# PWM.net
KiCad netlist of a schematic drawn in Altium Designer
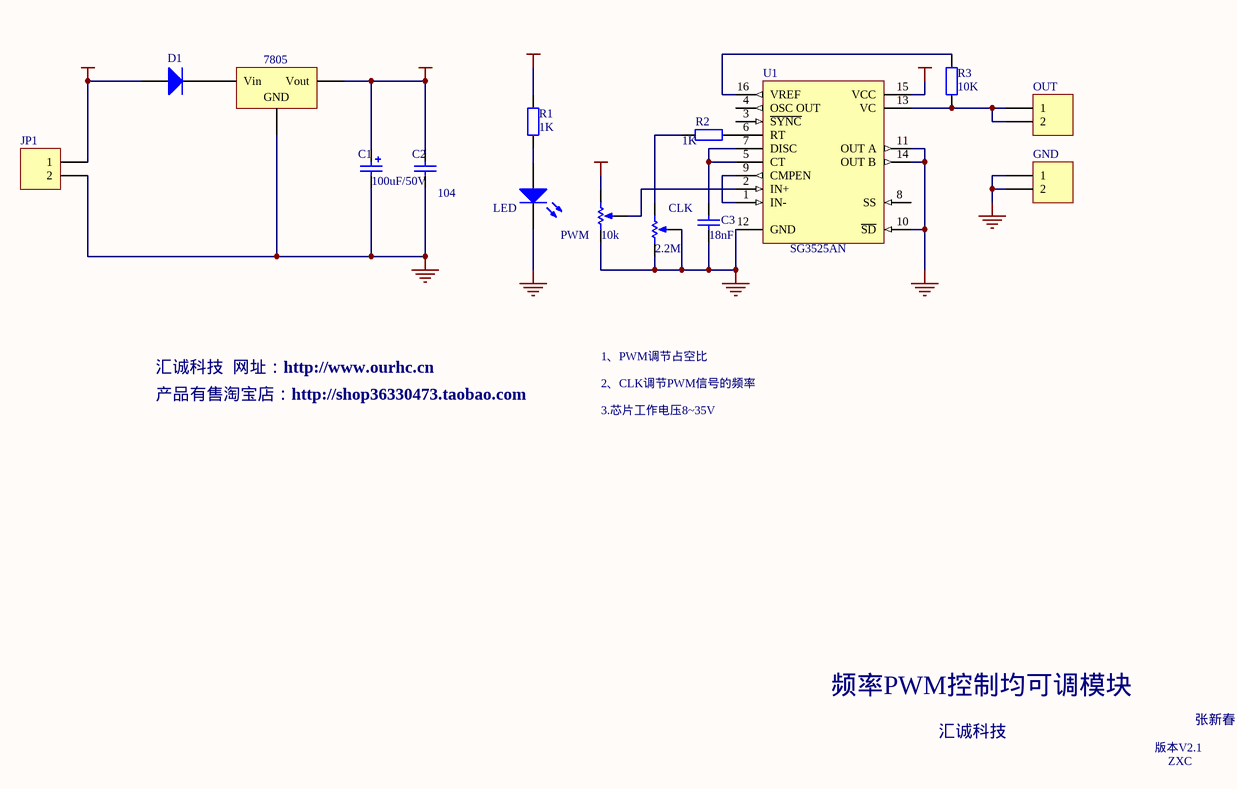
[diagram p0: 频率PWM控制均可调模块.SchDoc]

(export (version "E")
  (design (tool "Eeschema 10.0.6"))
  (components
    (comp (ref "7805")
      (value "SDWYG")
      (footprint "WYG")
      (description "三端稳压器")
      (fields (field (name "PUBLISHER") "Altium Limited"))
      (libsource (lib "zxcourhc") (part "SDWYG"))
    )
    (comp (ref "C1")
      (value "100uF/50V")
      (footprint "C-DJ-6")
      (description "电解电容")
      (fields (field (name "Comment") "DJDR") (field (name "PUBLISHER") "Altium Limited"))
      (libsource (lib "zxcourhc") (part "DJDR"))
    )
    (comp (ref "C2")
      (value "104")
      (footprint "CPDR")
      (description "瓷片电容")
      (fields (field (name "Comment") "CPDR") (field (name "PUBLISHER") "Altium Limited"))
      (libsource (lib "zxcourhc") (part "CPDR"))
    )
    (comp (ref "C3")
      (value "18nF")
      (footprint "CPDR")
      (description "Capacitor (Semiconductor SIM Model)")
      (fields (field (name "Comment") "Cap Semi") (field (name "PUBLISHER") "Altium Limited"))
      (libsource (lib "Miscellaneous Devices") (part "Cap Semi"))
    )
    (comp (ref "CLK")
      (value "2.2M")
      (footprint "SIP3-D")
      (description "Potentiometer")
      (fields (field (name "Comment") "RPot") (field (name "PUBLISHER") "Altium Limited"))
      (libsource (lib "Miscellaneous Devices") (part "RPot"))
    )
    (comp (ref "D1")
      (value "Diode 1N4007")
      (footprint "D-ZL-10")
      (description "1 Amp General Purpose Rectifier")
      (fields (field (name "PUBLISHER") "Altium Limited"))
      (libsource (lib "Miscellaneous Devices") (part "Diode 1N4007"))
    )
    (comp (ref "GND")
      (value "Header 2")
      (footprint "HDR1X2")
      (description "Header, 2-Pin")
      (fields (field (name "PUBLISHER") "Altium Limited"))
      (libsource (lib "Miscellaneous Connectors") (part "Header 2"))
    )
    (comp (ref "JP1")
      (value "PZ_2")
      (footprint "zxcourhc:JK128_2")
      (description "排针——2")
      (fields (field (name "PUBLISHER") "Altium Limited"))
      (libsource (lib "zxcourhc") (part "PZ_2"))
    )
    (comp (ref "LED")
      (value "LED2")
      (footprint "LED_D")
      (description "Typical RED, GREEN, YELLOW, AMBER GaAs LED")
      (fields (field (name "PUBLISHER") "Altium Limited"))
      (libsource (lib "Miscellaneous Devices") (part "LED2"))
    )
    (comp (ref "OUT")
      (value "Header 2")
      (footprint "HDR1X2")
      (description "Header, 2-Pin")
      (fields (field (name "PUBLISHER") "Altium Limited"))
      (libsource (lib "Miscellaneous Connectors") (part "Header 2"))
    )
    (comp (ref "PWM")
      (value "10k")
      (footprint "SIP3-D")
      (description "Potentiometer")
      (fields (field (name "Comment") "RPot") (field (name "PUBLISHER") "Altium Limited"))
      (libsource (lib "Miscellaneous Devices") (part "RPot"))
    )
    (comp (ref "R1")
      (value "1K")
      (footprint "AXIAL-0.4")
      (description "Resistor")
      (fields (field (name "Comment") "Res2") (field (name "PUBLISHER") "Altium Limited"))
      (libsource (lib "") (part "Res2_2"))
    )
    (comp (ref "R2")
      (value "1K")
      (footprint "AXIAL-0.4")
      (description "Resistor")
      (fields (field (name "Comment") "Res2") (field (name "PUBLISHER") "Altium Limited"))
      (libsource (lib "Miscellaneous Devices") (part "Res2"))
    )
    (comp (ref "R3")
      (value "10K")
      (footprint "AXIAL-0.4")
      (description "Resistor")
      (fields (field (name "Comment") "Res2") (field (name "PUBLISHER") "Altium Limited"))
      (libsource (lib "") (part "Res2_1"))
    )
    (comp (ref "U1")
      (value "SG3525AN")
      (footprint "DIP16")
      (description "Pulse Width Modulator Control Circuit")
      (fields (field (name "PUBLISHER") "Altium Limited"))
      (libsource (lib "ON Semi Power Mgt SMPS Controller") (part "SG3525AN"))
    )
  )
  (nets
    (net (code "1") (name "GND") (class "Default")
      (node (ref "7805") (pin "3") (pinfunction "GND_3") (pintype "passive"))
      (node (ref "C1") (pin "2") (pinfunction "2_2") (pintype "passive"))
      (node (ref "C2") (pin "1") (pinfunction "1_1") (pintype "passive"))
      (node (ref "C3") (pin "2") (pinfunction "2_2") (pintype "passive"))
      (node (ref "CLK") (pin "1") (pinfunction "TOP_1") (pintype "passive"))
      (node (ref "CLK") (pin "3") (pinfunction "TAP_3") (pintype "passive"))
      (node (ref "GND") (pin "1") (pinfunction "1_1") (pintype "passive"))
      (node (ref "GND") (pin "2") (pinfunction "2_2") (pintype "passive"))
      (node (ref "JP1") (pin "2") (pinfunction "2_2") (pintype "passive"))
      (node (ref "LED") (pin "2") (pinfunction "K_2") (pintype "passive"))
      (node (ref "PWM") (pin "1") (pinfunction "TOP_1") (pintype "passive"))
      (node (ref "U1") (pin "10") (pinfunction "~{SD}_10") (pintype "input"))
      (node (ref "U1") (pin "11") (pinfunction "OUT_A_11") (pintype "output"))
      (node (ref "U1") (pin "12") (pinfunction "GND_12") (pintype "power_in"))
      (node (ref "U1") (pin "14") (pinfunction "OUT_B_14") (pintype "output"))
    )
    (net (code "2") (name "Net-(7805-Vin)") (class "Default")
      (node (ref "7805") (pin "1") (pinfunction "Vin_1") (pintype "passive"))
      (node (ref "D1") (pin "2") (pinfunction "K_2") (pintype "passive"))
    )
    (net (code "3") (name "Net-(CLK-BOT)") (class "Default")
      (node (ref "CLK") (pin "2") (pinfunction "BOT_2") (pintype "passive"))
      (node (ref "R2") (pin "2") (pinfunction "2_2") (pintype "passive"))
    )
    (net (code "4") (name "Net-(LED-A)") (class "Default")
      (node (ref "LED") (pin "1") (pinfunction "A_1") (pintype "passive"))
      (node (ref "R1") (pin "2") (pinfunction "2_2") (pintype "passive"))
    )
    (net (code "5") (name "Net-(PWM-TAP)") (class "Default")
      (node (ref "PWM") (pin "3") (pinfunction "TAP_3") (pintype "passive"))
      (node (ref "U1") (pin "2") (pinfunction "IN+_2") (pintype "input"))
    )
    (net (code "6") (name "Net-(U1-CMPEN)") (class "Default")
      (node (ref "U1") (pin "1") (pinfunction "IN-_1") (pintype "input"))
      (node (ref "U1") (pin "9") (pinfunction "CMPEN_9") (pintype "output"))
    )
    (net (code "7") (name "Net-(U1-CT)") (class "Default")
      (node (ref "C3") (pin "1") (pinfunction "1_1") (pintype "passive"))
      (node (ref "U1") (pin "5") (pinfunction "CT_5") (pintype "passive"))
      (node (ref "U1") (pin "7") (pinfunction "DISC_7") (pintype "open_collector"))
    )
    (net (code "8") (name "Net-(U1-RT)") (class "Default")
      (node (ref "R2") (pin "1") (pinfunction "1_1") (pintype "passive"))
      (node (ref "U1") (pin "6") (pinfunction "RT_6") (pintype "passive"))
    )
    (net (code "9") (name "Net-(U1-VC)") (class "Default")
      (node (ref "OUT") (pin "1") (pinfunction "1_1") (pintype "passive"))
      (node (ref "OUT") (pin "2") (pinfunction "2_2") (pintype "passive"))
      (node (ref "R3") (pin "1") (pinfunction "1_1") (pintype "passive"))
      (node (ref "U1") (pin "13") (pinfunction "VC_13") (pintype "power_in"))
    )
    (net (code "10") (name "Net-(U1-VREF)") (class "Default")
      (node (ref "R3") (pin "2") (pinfunction "2_2") (pintype "passive"))
      (node (ref "U1") (pin "16") (pinfunction "VREF_16") (pintype "output"))
    )
    (net (code "11") (name "VCC1") (class "Default")
      (node (ref "D1") (pin "1") (pinfunction "A_1") (pintype "passive"))
      (node (ref "JP1") (pin "1") (pinfunction "1_1") (pintype "passive"))
      (node (ref "U1") (pin "15") (pinfunction "VCC_15") (pintype "power_in"))
    )
    (net (code "12") (name "VCC2") (class "Default")
      (node (ref "7805") (pin "2") (pinfunction "Vout_2") (pintype "passive"))
      (node (ref "C1") (pin "1") (pinfunction "1_1") (pintype "passive"))
      (node (ref "C2") (pin "2") (pinfunction "2_2") (pintype "passive"))
      (node (ref "PWM") (pin "2") (pinfunction "BOT_2") (pintype "passive"))
      (node (ref "R1") (pin "1") (pinfunction "1_1") (pintype "passive"))
    )
    (net (code "13") (name "unconnected-(U1-OSC_OUT-Pad4)") (class "Default")
      (node (ref "U1") (pin "4") (pinfunction "OSC_OUT_4") (pintype "output"))
    )
    (net (code "14") (name "unconnected-(U1-SS-Pad8)") (class "Default")
      (node (ref "U1") (pin "8") (pinfunction "SS_8") (pintype "input"))
    )
    (net (code "15") (name "unconnected-(U1-~{SYNC}-Pad3)") (class "Default")
      (node (ref "U1") (pin "3") (pinfunction "~{SYNC}_3") (pintype "input"))
    )
  )
)
